# 09_Power_Supply.net
KiCad netlist of a schematic drawn in Altium Designer
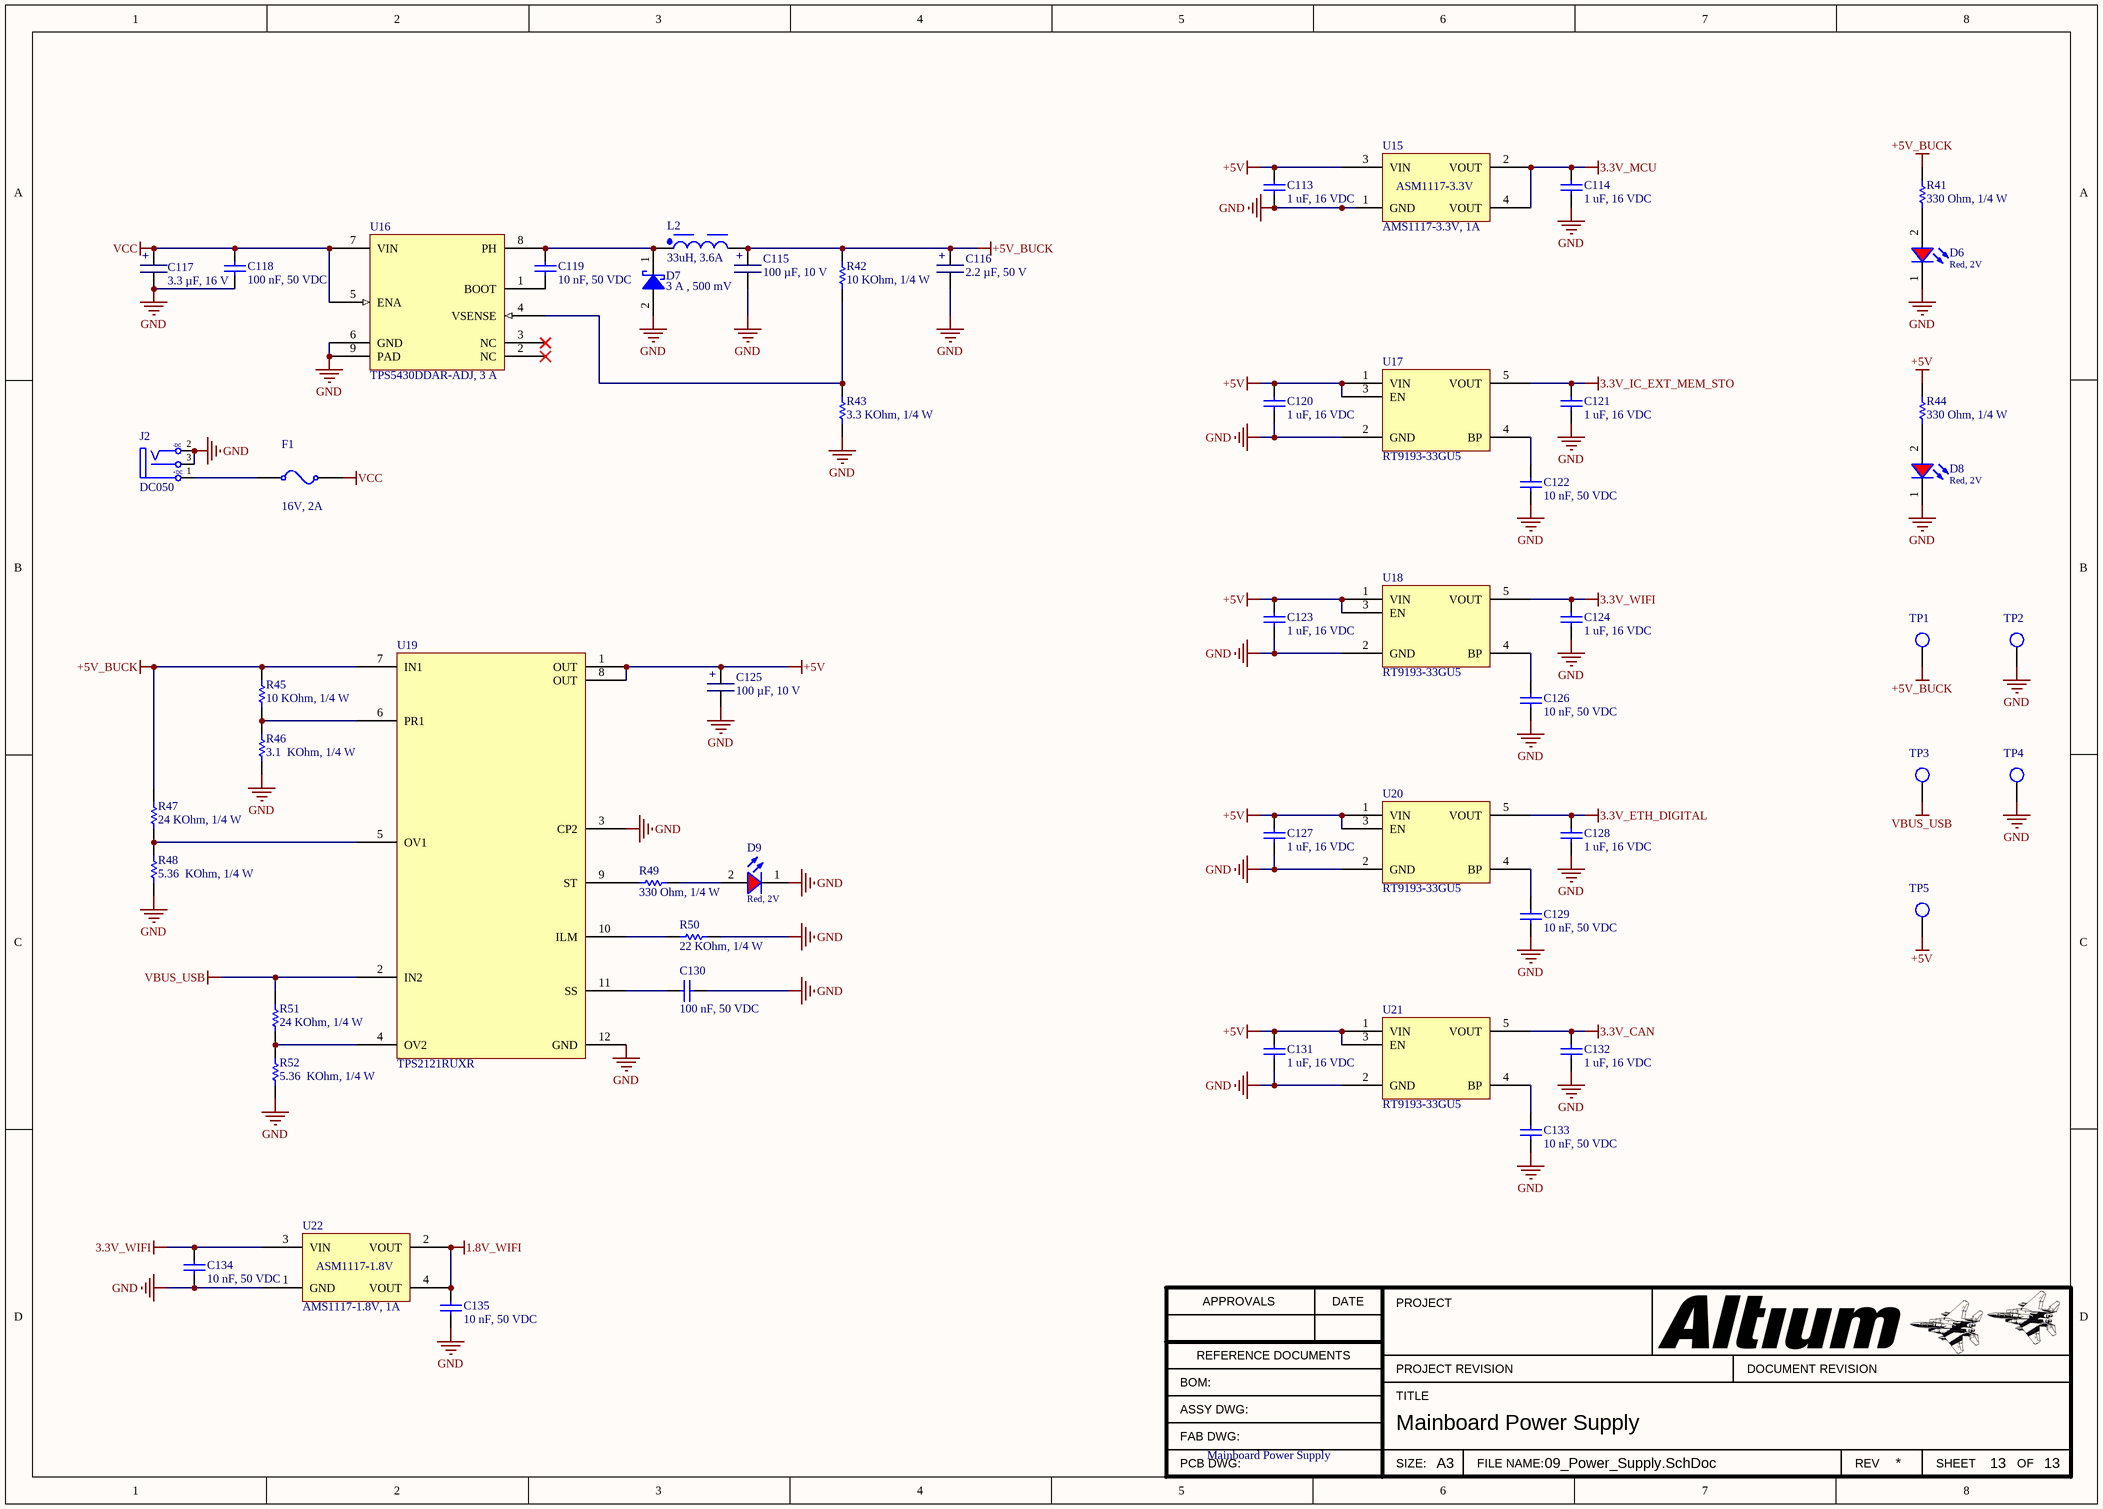
[diagram p0: 09_Power_Supply.SchDoc]

(export (version "E")
  (design (tool "Eeschema 10.0.6"))
  (components
    (comp (ref "C113")
      (value "1 uF, 16 VDC")
      (footprint "CAP_0603")
      (description "CAP, size 0603, 1 uF, 16 VDC")
      (fields (field (name "TOLERANCE") "+/-10%"))
      (libsource (lib "Altium_Ceramic_Cap") (part "0106031051016"))
    )
    (comp (ref "C114")
      (value "1 uF, 16 VDC")
      (footprint "CAP_0603")
      (description "CAP, size 0603, 1 uF, 16 VDC")
      (fields (field (name "TOLERANCE") "+/-10%"))
      (libsource (lib "Altium_Ceramic_Cap") (part "0106031051016"))
    )
    (comp (ref "C115")
      (value "100 µF, 10 V")
      (footprint "TANTALUM SMD C")
      (description "CAP TANT 100uF 10% 10V 2312")
      (libsource (lib "Altium_Tanta_Capacitor") (part "01231210710"))
    )
    (comp (ref "C116")
      (value "2.2 µF, 50 V")
      (footprint "TANTALUM SMD B")
      (description "CAP TANT 2.2uF 10% 50V 1411")
      (libsource (lib "Altium_Tanta_Capacitor") (part "01141122510"))
    )
    (comp (ref "C117")
      (value "3.3 µF, 16 V")
      (footprint "TANTALUM SMD A")
      (description "CAP TANT 3.3uF 10% 16V 1206")
      (libsource (lib "Altium_Tanta_Capacitor") (part "01120633510"))
    )
    (comp (ref "C118")
      (value "100 nF, 50 VDC")
      (footprint "CAP_0603")
      (description "CAP, size 0603, 100 nF, 50 VDC")
      (fields (field (name "TOLERANCE") "+/-10%"))
      (libsource (lib "Altium_Ceramic_Cap") (part "0106031041050"))
    )
    (comp (ref "C119")
      (value "10 nF, 50 VDC")
      (footprint "CAP_0603")
      (description "CAP, size 0603, 10 nF, 50 VDC")
      (fields (field (name "TOLERANCE") "+/-10%"))
      (libsource (lib "Altium_Ceramic_Cap") (part "0106031031050"))
    )
    (comp (ref "C120")
      (value "1 uF, 16 VDC")
      (footprint "CAP_0603")
      (description "CAP, size 0603, 1 uF, 16 VDC")
      (fields (field (name "TOLERANCE") "+/-10%"))
      (libsource (lib "Altium_Ceramic_Cap") (part "0106031051016"))
    )
    (comp (ref "C121")
      (value "1 uF, 16 VDC")
      (footprint "CAP_0603")
      (description "CAP, size 0603, 1 uF, 16 VDC")
      (fields (field (name "TOLERANCE") "+/-10%"))
      (libsource (lib "Altium_Ceramic_Cap") (part "0106031051016"))
    )
    (comp (ref "C122")
      (value "10 nF, 50 VDC")
      (footprint "CAP_0603")
      (description "CAP, size 0603, 10 nF, 50 VDC")
      (fields (field (name "TOLERANCE") "+/-5%"))
      (libsource (lib "Altium_Ceramic_Cap") (part "0106031030550"))
    )
    (comp (ref "C123")
      (value "1 uF, 16 VDC")
      (footprint "CAP_0603")
      (description "CAP, size 0603, 1 uF, 16 VDC")
      (fields (field (name "TOLERANCE") "+/-10%"))
      (libsource (lib "Altium_Ceramic_Cap") (part "0106031051016"))
    )
    (comp (ref "C124")
      (value "1 uF, 16 VDC")
      (footprint "CAP_0603")
      (description "CAP, size 0603, 1 uF, 16 VDC")
      (fields (field (name "TOLERANCE") "+/-10%"))
      (libsource (lib "Altium_Ceramic_Cap") (part "0106031051016"))
    )
    (comp (ref "C125")
      (value "100 µF, 10 V")
      (footprint "TANTALUM SMD C")
      (description "CAP TANT 100uF 10% 10V 2312")
      (libsource (lib "Altium_Tanta_Capacitor") (part "01231210710"))
    )
    (comp (ref "C126")
      (value "10 nF, 50 VDC")
      (footprint "CAP_0603")
      (description "CAP, size 0603, 10 nF, 50 VDC")
      (fields (field (name "TOLERANCE") "+/-5%"))
      (libsource (lib "Altium_Ceramic_Cap") (part "0106031030550"))
    )
    (comp (ref "C127")
      (value "1 uF, 16 VDC")
      (footprint "CAP_0603")
      (description "CAP, size 0603, 1 uF, 16 VDC")
      (fields (field (name "TOLERANCE") "+/-10%"))
      (libsource (lib "Altium_Ceramic_Cap") (part "0106031051016"))
    )
    (comp (ref "C128")
      (value "1 uF, 16 VDC")
      (footprint "CAP_0603")
      (description "CAP, size 0603, 1 uF, 16 VDC")
      (fields (field (name "TOLERANCE") "+/-10%"))
      (libsource (lib "Altium_Ceramic_Cap") (part "0106031051016"))
    )
    (comp (ref "C129")
      (value "10 nF, 50 VDC")
      (footprint "CAP_0603")
      (description "CAP, size 0603, 10 nF, 50 VDC")
      (fields (field (name "TOLERANCE") "+/-5%"))
      (libsource (lib "Altium_Ceramic_Cap") (part "0106031030550"))
    )
    (comp (ref "C130")
      (value "100 nF, 50 VDC")
      (footprint "CAP_0603")
      (description "CAP, size 0603, 100 nF, 50 VDC")
      (fields (field (name "TOLERANCE") "+/-10%"))
      (libsource (lib "Altium_Ceramic_Cap") (part "0106031041050"))
    )
    (comp (ref "C131")
      (value "1 uF, 16 VDC")
      (footprint "CAP_0603")
      (description "CAP, size 0603, 1 uF, 16 VDC")
      (fields (field (name "TOLERANCE") "+/-10%"))
      (libsource (lib "Altium_Ceramic_Cap") (part "0106031051016"))
    )
    (comp (ref "C132")
      (value "1 uF, 16 VDC")
      (footprint "CAP_0603")
      (description "CAP, size 0603, 1 uF, 16 VDC")
      (fields (field (name "TOLERANCE") "+/-10%"))
      (libsource (lib "Altium_Ceramic_Cap") (part "0106031051016"))
    )
    (comp (ref "C133")
      (value "10 nF, 50 VDC")
      (footprint "CAP_0603")
      (description "CAP, size 0603, 10 nF, 50 VDC")
      (fields (field (name "TOLERANCE") "+/-5%"))
      (libsource (lib "Altium_Ceramic_Cap") (part "0106031030550"))
    )
    (comp (ref "C134")
      (value "10 nF, 50 VDC")
      (footprint "CAP_0603")
      (description "CAP, size 0603, 10 nF, 50 VDC")
      (fields (field (name "TOLERANCE") "+/-5%"))
      (libsource (lib "Altium_Ceramic_Cap") (part "0106031030550"))
    )
    (comp (ref "C135")
      (value "10 nF, 50 VDC")
      (footprint "CAP_0603")
      (description "CAP, size 0603, 10 nF, 50 VDC")
      (fields (field (name "TOLERANCE") "+/-5%"))
      (libsource (lib "Altium_Ceramic_Cap") (part "0106031030550"))
    )
    (comp (ref "D6")
      (value "Red, 2V")
      (footprint "WL-SMCW_0603_H=0.7mm")
      (description "WL-SMCW SMT Mono-color Chip LED Blur, size 0603, Red, 2V, 140deg")
      (libsource (lib "Altium_LED") (part "160603RedBlur"))
    )
    (comp (ref "D7")
      (value "3 A , 500 mV")
      (footprint "SMC (DO-214AB)")
      (description "Schottky Diodes & Rectifiers 3.0 Amp 40 Volt")
      (fields (field (name "MANUFACTURER") "Vishay Semiconductors"))
      (libsource (lib "Altium_Diode") (part "SS34"))
    )
    (comp (ref "D8")
      (value "Red, 2V")
      (footprint "WL-SMCW_0603_H=0.7mm")
      (description "WL-SMCW SMT Mono-color Chip LED Blur, size 0603, Red, 2V, 140deg")
      (libsource (lib "Altium_LED") (part "160603RedBlur"))
    )
    (comp (ref "D9")
      (value "Red, 2V")
      (footprint "WL-SMCW_0603_H=0.7mm")
      (description "WL-SMCW SMT Mono-color Chip LED Blur, size 0603, Red, 2V, 140deg")
      (libsource (lib "Altium_LED") (part "160603RedBlur"))
    )
    (comp (ref "F1")
      (value "16V, 2A")
      (footprint "Fuse_SMD_1812")
      (description "Resettable Fuse, Size 1812, 16V, 2A")
      (fields (field (name "MANUFACTURER") "Littelfuse"))
      (libsource (lib "Altium_Fuse") (part "061812200016"))
    )
    (comp (ref "J2")
      (value "DC050")
      (footprint "DC050")
      (fields (field (name "MANUFACTURER") "OEM"))
      (libsource (lib "Altium_Other") (part "DC050"))
    )
    (comp (ref "L2")
      (value "33uH, 3.6A")
      (footprint "WE-PD_1280")
      (description "WE-PD SMT Power Inductor, size 1280, 33uH, 3.6A, 53mOhm")
      (fields
        (field (name "MANUFACTURER PART NUMBER") "744770133")
        (field (name "MANUFACTURER") "Wurth Elektronik")
      )
      (libsource (lib "Altium_Coil_Inductor") (part "744770133"))
    )
    (comp (ref "R41")
      (value "330 Ohm, 1/4 W")
      (footprint "resistor_0603")
      (description "RES, size 0603, 330 Ohm, 1/4 W")
      (libsource (lib "Altium_Resistor") (part "0006033311"))
    )
    (comp (ref "R42")
      (value "10 KOhm, 1/4 W")
      (footprint "resistor_0603")
      (description "RES, size 0603, 10 KOhm, 1/4 W")
      (libsource (lib "Altium_Resistor") (part "0006031031"))
    )
    (comp (ref "R43")
      (value "3.3 KOhm, 1/4 W")
      (footprint "resistor_0603")
      (description "RES, size 0603, 3.3 KOhm, 1/4 W")
      (libsource (lib "Altium_Resistor") (part "0006033325"))
    )
    (comp (ref "R44")
      (value "330 Ohm, 1/4 W")
      (footprint "resistor_0603")
      (description "RES, size 0603, 330 Ohm, 1/4 W")
      (libsource (lib "Altium_Resistor") (part "0006033311"))
    )
    (comp (ref "R45")
      (value "10 KOhm, 1/4 W")
      (footprint "resistor_0603")
      (description "RES, size 0603, 10 KOhm, 1/4 W")
      (libsource (lib "Altium_Resistor") (part "0006031031"))
    )
    (comp (ref "R46")
      (value "3.1  KOhm, 1/4 W")
      (footprint "resistor_0603")
      (description "RES, size 0603, 3.1  KOhm, 1/4 W")
      (libsource (lib "Altium_Resistor") (part "0006033121"))
    )
    (comp (ref "R47")
      (value "24 KOhm, 1/4 W")
      (footprint "resistor_0603")
      (description "RES, size 0603, 24 KOhm, 1/4 W")
      (libsource (lib "Altium_Resistor") (part "0006032431"))
    )
    (comp (ref "R48")
      (value "5.36  KOhm, 1/4 W")
      (footprint "resistor_0603")
      (description "RES, size 0603, 5.36  KOhm, 1/4 W")
      (libsource (lib "Altium_Resistor") (part "00060353611"))
    )
    (comp (ref "R49")
      (value "330 Ohm, 1/4 W")
      (footprint "resistor_0603")
      (description "RES, size 0603, 330 Ohm, 1/4 W")
      (libsource (lib "Altium_Resistor") (part "0006033311"))
    )
    (comp (ref "R50")
      (value "22 KOhm, 1/4 W")
      (footprint "resistor_0603")
      (description "RES, size 0603, 22 KOhm, 1/4 W")
      (libsource (lib "Altium_Resistor") (part "0006032231"))
    )
    (comp (ref "R51")
      (value "24 KOhm, 1/4 W")
      (footprint "resistor_0603")
      (description "RES, size 0603, 24 KOhm, 1/4 W")
      (libsource (lib "Altium_Resistor") (part "0006032431"))
    )
    (comp (ref "R52")
      (value "5.36  KOhm, 1/4 W")
      (footprint "resistor_0603")
      (description "RES, size 0603, 5.36  KOhm, 1/4 W")
      (libsource (lib "Altium_Resistor") (part "00060353611"))
    )
    (comp (ref "TP1")
      (value "Test point")
      (footprint "TP")
      (libsource (lib "Altium_Other") (part "Test point"))
    )
    (comp (ref "TP2")
      (value "Test point")
      (footprint "TP")
      (libsource (lib "Altium_Other") (part "Test point"))
    )
    (comp (ref "TP3")
      (value "Test point")
      (footprint "TP")
      (libsource (lib "Altium_Other") (part "Test point"))
    )
    (comp (ref "TP4")
      (value "Test point")
      (footprint "TP")
      (libsource (lib "Altium_Other") (part "Test point"))
    )
    (comp (ref "TP5")
      (value "Test point")
      (footprint "TP")
      (libsource (lib "Altium_Other") (part "Test point"))
    )
    (comp (ref "U15")
      (value "AMS1117-3.3V, 1A")
      (footprint "AMS1117-3.3V SOT223")
      (description "AMS1117-3.3V, OUT 3.3V 1A.")
      (fields (field (name "MANUFACTURER") "AMS"))
      (libsource (lib "Altium_Power_Supply_IC") (part "AMS1117-3.3V"))
    )
    (comp (ref "U16")
      (value "TPS5430DDAR-ADJ, 3 A")
      (footprint "TPS5430DDAR")
      (description "5.5V to 36V Input, 3A, 500kHz Step-Down Converter")
      (fields (field (name "MANUFACTURER") "Texas Instruments"))
      (libsource (lib "TPS543xx_family") (part "TPS5430DDAR"))
    )
    (comp (ref "U17")
      (value "RT9193-33GU5")
      (footprint "RT9193-xxGU5")
      (description "LDO Voltage Regulators 300mA, Ultra-Low Noise, Ultra-Fast CMOS LDO Regulator, SC-70-5, 3.3V")
      (fields (field (name "MANUFACTURER") "Richtek"))
      (libsource (lib "Altium_Power_Supply_IC") (part "RT9193-33GU5"))
    )
    (comp (ref "U18")
      (value "RT9193-33GU5")
      (footprint "RT9193-xxGU5")
      (description "LDO Voltage Regulators 300mA, Ultra-Low Noise, Ultra-Fast CMOS LDO Regulator, SC-70-5, 3.3V")
      (fields (field (name "MANUFACTURER") "Richtek"))
      (libsource (lib "Altium_Power_Supply_IC") (part "RT9193-33GU5"))
    )
    (comp (ref "U19")
      (value "TPS2121RUXR")
      (footprint "TPS2121RUXR")
      (description "2.7-V to 22-V, 56-mΩ, 4.5-A, power mux with seamless switchover")
      (fields (field (name "MANUFACTURER") "Texas Instruments"))
      (libsource (lib "Power_Mux") (part "TPS2121RUXR"))
    )
    (comp (ref "U20")
      (value "RT9193-33GU5")
      (footprint "RT9193-xxGU5")
      (description "LDO Voltage Regulators 300mA, Ultra-Low Noise, Ultra-Fast CMOS LDO Regulator, SC-70-5, 3.3V")
      (fields (field (name "MANUFACTURER") "Richtek"))
      (libsource (lib "Altium_Power_Supply_IC") (part "RT9193-33GU5"))
    )
    (comp (ref "U21")
      (value "RT9193-33GU5")
      (footprint "RT9193-xxGU5")
      (description "LDO Voltage Regulators 300mA, Ultra-Low Noise, Ultra-Fast CMOS LDO Regulator, SC-70-5, 3.3V")
      (fields (field (name "MANUFACTURER") "Richtek"))
      (libsource (lib "Altium_Power_Supply_IC") (part "RT9193-33GU5"))
    )
    (comp (ref "U22")
      (value "AMS1117-1.8V, 1A")
      (footprint "AMS1117-1.8V SOT223")
      (description "AMS1117-1.8V, OUT 1.8V 1A.")
      (fields (field (name "MANUFACTURER") "AMS"))
      (libsource (lib "AMS_family") (part "AMS1117-1.8V"))
    )
  )
  (nets
    (net (code "1") (name "+5V") (class "Default")
      (node (ref "C113") (pin "2") (pinfunction "2_2") (pintype "passive"))
      (node (ref "C120") (pin "2") (pinfunction "2_2") (pintype "passive"))
      (node (ref "C123") (pin "2") (pinfunction "2_2") (pintype "passive"))
      (node (ref "C125") (pin "2") (pinfunction "2_2") (pintype "passive"))
      (node (ref "C127") (pin "2") (pinfunction "2_2") (pintype "passive"))
      (node (ref "C131") (pin "2") (pinfunction "2_2") (pintype "passive"))
      (node (ref "R44") (pin "2") (pinfunction "2_2") (pintype "passive"))
      (node (ref "TP5") (pin "1") (pinfunction "27_1") (pintype "passive"))
      (node (ref "U15") (pin "3") (pinfunction "VIN_3") (pintype "passive"))
      (node (ref "U17") (pin "1") (pinfunction "VIN_1") (pintype "power_in"))
      (node (ref "U17") (pin "3") (pinfunction "EN_3") (pintype "power_in"))
      (node (ref "U18") (pin "1") (pinfunction "VIN_1") (pintype "power_in"))
      (node (ref "U18") (pin "3") (pinfunction "EN_3") (pintype "power_in"))
      (node (ref "U19") (pin "1") (pinfunction "OUT_1") (pintype "passive"))
      (node (ref "U19") (pin "8") (pinfunction "OUT_8") (pintype "passive"))
      (node (ref "U20") (pin "1") (pinfunction "VIN_1") (pintype "power_in"))
      (node (ref "U20") (pin "3") (pinfunction "EN_3") (pintype "power_in"))
      (node (ref "U21") (pin "1") (pinfunction "VIN_1") (pintype "power_in"))
      (node (ref "U21") (pin "3") (pinfunction "EN_3") (pintype "power_in"))
    )
    (net (code "2") (name "+5V_BUCK") (class "Default")
      (node (ref "C115") (pin "2") (pinfunction "2_2") (pintype "passive"))
      (node (ref "C116") (pin "2") (pinfunction "2_2") (pintype "passive"))
      (node (ref "L2") (pin "2") (pinfunction "2_2") (pintype "passive"))
      (node (ref "R41") (pin "2") (pinfunction "2_2") (pintype "passive"))
      (node (ref "R42") (pin "2") (pinfunction "2_2") (pintype "passive"))
      (node (ref "R45") (pin "2") (pinfunction "2_2") (pintype "passive"))
      (node (ref "R47") (pin "2") (pinfunction "2_2") (pintype "passive"))
      (node (ref "TP1") (pin "1") (pinfunction "27_1") (pintype "passive"))
      (node (ref "U19") (pin "7") (pinfunction "IN1_7") (pintype "passive"))
    )
    (net (code "3") (name "1.8V_WIFI") (class "Default")
      (node (ref "C135") (pin "2") (pinfunction "2_2") (pintype "passive"))
      (node (ref "U22") (pin "2") (pinfunction "VOUT_2") (pintype "passive"))
      (node (ref "U22") (pin "4") (pinfunction "VOUT_4") (pintype "power_in"))
    )
    (net (code "4") (name "3.3V_CAN") (class "Default")
      (node (ref "C132") (pin "2") (pinfunction "2_2") (pintype "passive"))
      (node (ref "U21") (pin "5") (pinfunction "VOUT_5") (pintype "power_in"))
    )
    (net (code "5") (name "3.3V_ETH_DIGITAL") (class "Default")
      (node (ref "C128") (pin "2") (pinfunction "2_2") (pintype "passive"))
      (node (ref "U20") (pin "5") (pinfunction "VOUT_5") (pintype "power_in"))
    )
    (net (code "6") (name "3.3V_IC_EXT_MEM_STO") (class "Default")
      (node (ref "C121") (pin "2") (pinfunction "2_2") (pintype "passive"))
      (node (ref "U17") (pin "5") (pinfunction "VOUT_5") (pintype "power_in"))
    )
    (net (code "7") (name "3.3V_MCU") (class "Default")
      (node (ref "C114") (pin "2") (pinfunction "2_2") (pintype "passive"))
      (node (ref "U15") (pin "2") (pinfunction "VOUT_2") (pintype "passive"))
      (node (ref "U15") (pin "4") (pinfunction "VOUT_4") (pintype "power_in"))
    )
    (net (code "8") (name "3.3V_WIFI") (class "Default")
      (node (ref "C124") (pin "2") (pinfunction "2_2") (pintype "passive"))
      (node (ref "C134") (pin "2") (pinfunction "2_2") (pintype "passive"))
      (node (ref "U18") (pin "5") (pinfunction "VOUT_5") (pintype "power_in"))
      (node (ref "U22") (pin "3") (pinfunction "VIN_3") (pintype "passive"))
    )
    (net (code "9") (name "GND") (class "Default")
      (node (ref "C113") (pin "1") (pinfunction "1_1") (pintype "passive"))
      (node (ref "C114") (pin "1") (pinfunction "1_1") (pintype "passive"))
      (node (ref "C115") (pin "1") (pinfunction "1_1") (pintype "passive"))
      (node (ref "C116") (pin "1") (pinfunction "1_1") (pintype "passive"))
      (node (ref "C117") (pin "1") (pinfunction "1_1") (pintype "passive"))
      (node (ref "C118") (pin "1") (pinfunction "1_1") (pintype "passive"))
      (node (ref "C120") (pin "1") (pinfunction "1_1") (pintype "passive"))
      (node (ref "C121") (pin "1") (pinfunction "1_1") (pintype "passive"))
      (node (ref "C122") (pin "1") (pinfunction "1_1") (pintype "passive"))
      (node (ref "C123") (pin "1") (pinfunction "1_1") (pintype "passive"))
      (node (ref "C124") (pin "1") (pinfunction "1_1") (pintype "passive"))
      (node (ref "C125") (pin "1") (pinfunction "1_1") (pintype "passive"))
      (node (ref "C126") (pin "1") (pinfunction "1_1") (pintype "passive"))
      (node (ref "C127") (pin "1") (pinfunction "1_1") (pintype "passive"))
      (node (ref "C128") (pin "1") (pinfunction "1_1") (pintype "passive"))
      (node (ref "C129") (pin "1") (pinfunction "1_1") (pintype "passive"))
      (node (ref "C130") (pin "1") (pinfunction "1_1") (pintype "passive"))
      (node (ref "C131") (pin "1") (pinfunction "1_1") (pintype "passive"))
      (node (ref "C132") (pin "1") (pinfunction "1_1") (pintype "passive"))
      (node (ref "C133") (pin "1") (pinfunction "1_1") (pintype "passive"))
      (node (ref "C134") (pin "1") (pinfunction "1_1") (pintype "passive"))
      (node (ref "C135") (pin "1") (pinfunction "1_1") (pintype "passive"))
      (node (ref "D6") (pin "1") (pinfunction "K_1") (pintype "passive"))
      (node (ref "D7") (pin "2") (pinfunction "A_2") (pintype "passive"))
      (node (ref "D8") (pin "1") (pinfunction "K_1") (pintype "passive"))
      (node (ref "D9") (pin "1") (pinfunction "K_1") (pintype "passive"))
      (node (ref "J2") (pin "2") (pinfunction "TN_2") (pintype "passive"))
      (node (ref "J2") (pin "3") (pinfunction "S_3") (pintype "power_in"))
      (node (ref "R43") (pin "1") (pinfunction "1_1") (pintype "passive"))
      (node (ref "R46") (pin "1") (pinfunction "1_1") (pintype "passive"))
      (node (ref "R48") (pin "1") (pinfunction "1_1") (pintype "passive"))
      (node (ref "R50") (pin "2") (pinfunction "2_2") (pintype "passive"))
      (node (ref "R52") (pin "1") (pinfunction "1_1") (pintype "passive"))
      (node (ref "TP2") (pin "1") (pinfunction "27_1") (pintype "passive"))
      (node (ref "TP4") (pin "1") (pinfunction "27_1") (pintype "passive"))
      (node (ref "U15") (pin "1") (pinfunction "GND_1") (pintype "power_in"))
      (node (ref "U16") (pin "6") (pinfunction "GND_6") (pintype "power_in"))
      (node (ref "U16") (pin "9") (pinfunction "PAD_9") (pintype "power_in"))
      (node (ref "U17") (pin "2") (pinfunction "GND_2") (pintype "power_in"))
      (node (ref "U18") (pin "2") (pinfunction "GND_2") (pintype "power_in"))
      (node (ref "U19") (pin "12") (pinfunction "GND_12") (pintype "passive"))
      (node (ref "U19") (pin "3") (pinfunction "CP2_3") (pintype "passive"))
      (node (ref "U20") (pin "2") (pinfunction "GND_2") (pintype "power_in"))
      (node (ref "U21") (pin "2") (pinfunction "GND_2") (pintype "power_in"))
      (node (ref "U22") (pin "1") (pinfunction "GND_1") (pintype "power_in"))
    )
    (net (code "10") (name "Net-(D6-A)") (class "Default")
      (node (ref "D6") (pin "2") (pinfunction "A_2") (pintype "passive"))
      (node (ref "R41") (pin "1") (pinfunction "1_1") (pintype "passive"))
    )
    (net (code "11") (name "Net-(D7-K)") (class "Default")
      (node (ref "C119") (pin "2") (pinfunction "2_2") (pintype "passive"))
      (node (ref "D7") (pin "1") (pinfunction "K_1") (pintype "passive"))
      (node (ref "L2") (pin "1") (pinfunction "1_1") (pintype "passive"))
      (node (ref "U16") (pin "8") (pinfunction "PH_8") (pintype "power_in"))
    )
    (net (code "12") (name "Net-(D8-A)") (class "Default")
      (node (ref "D8") (pin "2") (pinfunction "A_2") (pintype "passive"))
      (node (ref "R44") (pin "1") (pinfunction "1_1") (pintype "passive"))
    )
    (net (code "13") (name "Net-(D9-A)") (class "Default")
      (node (ref "D9") (pin "2") (pinfunction "A_2") (pintype "passive"))
      (node (ref "R49") (pin "2") (pinfunction "2_2") (pintype "passive"))
    )
    (net (code "14") (name "Net-(J2-T)") (class "Default")
      (node (ref "F1") (pin "0") (pinfunction "0_0") (pintype "passive"))
      (node (ref "J2") (pin "1") (pinfunction "T_1") (pintype "passive"))
    )
    (net (code "15") (name "Net-(U16-BOOT)") (class "Default")
      (node (ref "C119") (pin "1") (pinfunction "1_1") (pintype "passive"))
      (node (ref "U16") (pin "1") (pinfunction "BOOT_1") (pintype "passive"))
    )
    (net (code "16") (name "Net-(U16-VSENSE)") (class "Default")
      (node (ref "R42") (pin "1") (pinfunction "1_1") (pintype "passive"))
      (node (ref "R43") (pin "2") (pinfunction "2_2") (pintype "passive"))
      (node (ref "U16") (pin "4") (pinfunction "VSENSE_4") (pintype "input"))
    )
    (net (code "17") (name "Net-(U17-BP)") (class "Default")
      (node (ref "C122") (pin "2") (pinfunction "2_2") (pintype "passive"))
      (node (ref "U17") (pin "4") (pinfunction "BP_4") (pintype "power_in"))
    )
    (net (code "18") (name "Net-(U18-BP)") (class "Default")
      (node (ref "C126") (pin "2") (pinfunction "2_2") (pintype "passive"))
      (node (ref "U18") (pin "4") (pinfunction "BP_4") (pintype "power_in"))
    )
    (net (code "19") (name "Net-(U19-ILM)") (class "Default")
      (node (ref "R50") (pin "1") (pinfunction "1_1") (pintype "passive"))
      (node (ref "U19") (pin "10") (pinfunction "ILM_10") (pintype "passive"))
    )
    (net (code "20") (name "Net-(U19-OV1)") (class "Default")
      (node (ref "R47") (pin "1") (pinfunction "1_1") (pintype "passive"))
      (node (ref "R48") (pin "2") (pinfunction "2_2") (pintype "passive"))
      (node (ref "U19") (pin "5") (pinfunction "OV1_5") (pintype "passive"))
    )
    (net (code "21") (name "Net-(U19-OV2)") (class "Default")
      (node (ref "R51") (pin "1") (pinfunction "1_1") (pintype "passive"))
      (node (ref "R52") (pin "2") (pinfunction "2_2") (pintype "passive"))
      (node (ref "U19") (pin "4") (pinfunction "OV2_4") (pintype "passive"))
    )
    (net (code "22") (name "Net-(U19-PR1)") (class "Default")
      (node (ref "R45") (pin "1") (pinfunction "1_1") (pintype "passive"))
      (node (ref "R46") (pin "2") (pinfunction "2_2") (pintype "passive"))
      (node (ref "U19") (pin "6") (pinfunction "PR1_6") (pintype "passive"))
    )
    (net (code "23") (name "Net-(U19-SS)") (class "Default")
      (node (ref "C130") (pin "2") (pinfunction "2_2") (pintype "passive"))
      (node (ref "U19") (pin "11") (pinfunction "SS_11") (pintype "passive"))
    )
    (net (code "24") (name "Net-(U19-ST)") (class "Default")
      (node (ref "R49") (pin "1") (pinfunction "1_1") (pintype "passive"))
      (node (ref "U19") (pin "9") (pinfunction "ST_9") (pintype "passive"))
    )
    (net (code "25") (name "Net-(U20-BP)") (class "Default")
      (node (ref "C129") (pin "2") (pinfunction "2_2") (pintype "passive"))
      (node (ref "U20") (pin "4") (pinfunction "BP_4") (pintype "power_in"))
    )
    (net (code "26") (name "Net-(U21-BP)") (class "Default")
      (node (ref "C133") (pin "2") (pinfunction "2_2") (pintype "passive"))
      (node (ref "U21") (pin "4") (pinfunction "BP_4") (pintype "power_in"))
    )
    (net (code "27") (name "VBUS_USB") (class "Default")
      (node (ref "R51") (pin "2") (pinfunction "2_2") (pintype "passive"))
      (node (ref "TP3") (pin "1") (pinfunction "27_1") (pintype "passive"))
      (node (ref "U19") (pin "2") (pinfunction "IN2_2") (pintype "passive"))
    )
    (net (code "28") (name "VCC") (class "Default")
      (node (ref "C117") (pin "2") (pinfunction "2_2") (pintype "passive"))
      (node (ref "C118") (pin "2") (pinfunction "2_2") (pintype "passive"))
      (node (ref "F1") (pin "1") (pinfunction "1_1") (pintype "passive"))
      (node (ref "U16") (pin "5") (pinfunction "ENA_5") (pintype "input"))
      (node (ref "U16") (pin "7") (pinfunction "VIN_7") (pintype "power_in"))
    )
    (net (code "29") (name "unconnected-(U16-NC-Pad2)") (class "Default")
      (node (ref "U16") (pin "2") (pinfunction "NC_2") (pintype "passive+no_connect"))
    )
    (net (code "30") (name "unconnected-(U16-NC-Pad3)") (class "Default")
      (node (ref "U16") (pin "3") (pinfunction "NC_3") (pintype "passive+no_connect"))
    )
  )
)
